# ClockV0_1.net
KiCad netlist of a schematic drawn in EAGLE
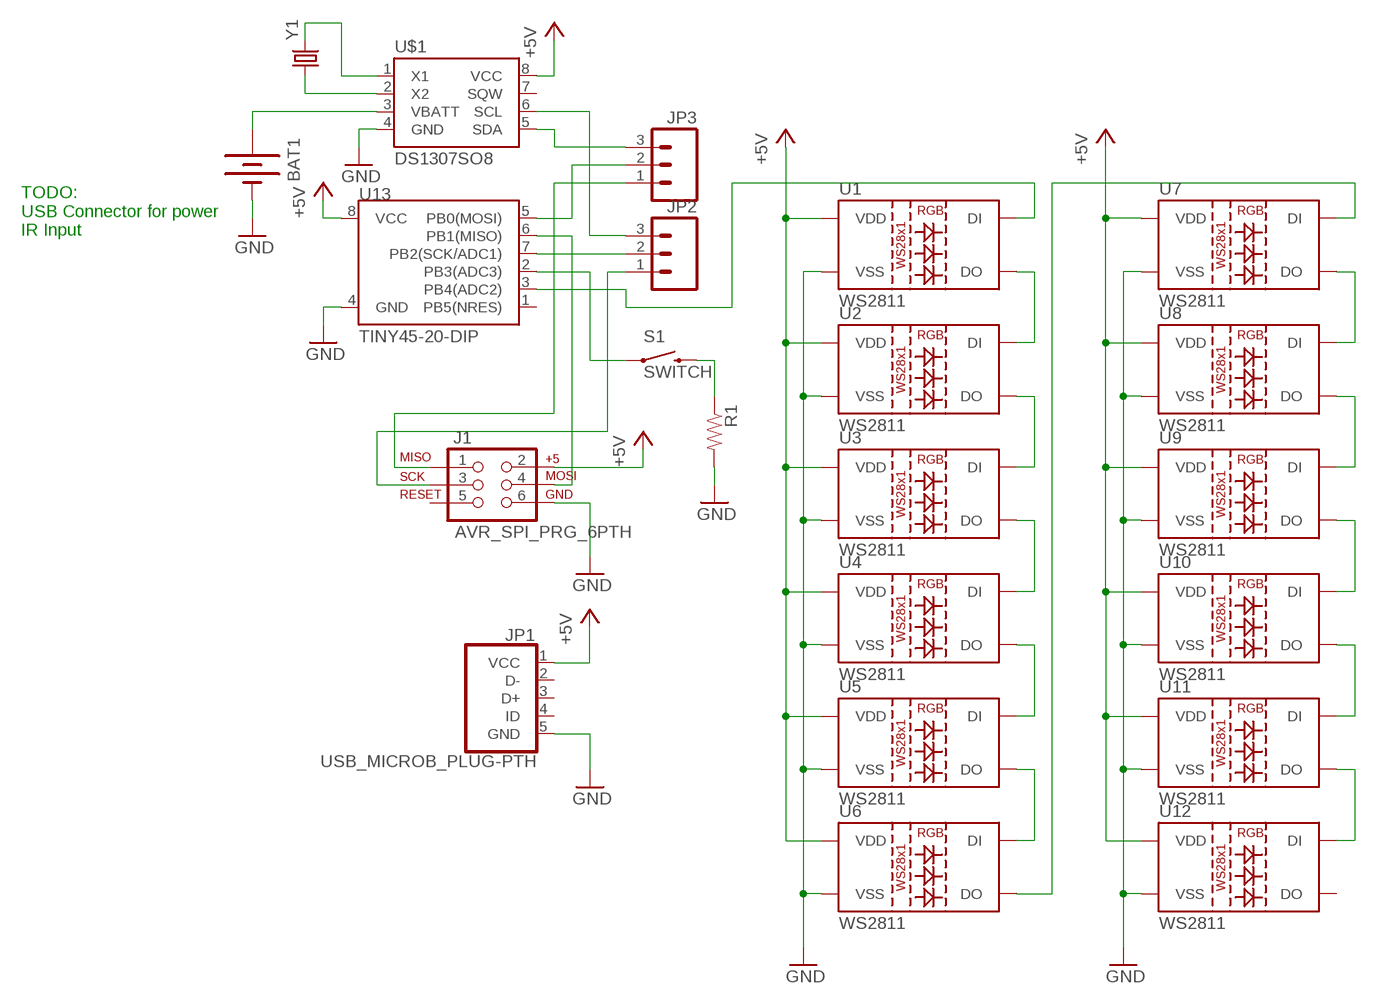
[diagram p0: schematic, sheet 1]

(export (version "E")
  (design (tool "Eeschema 10.0.6"))
  (components
    (comp (ref "BAT1")
      (value "BATTERY12PTH")
      (footprint "eagle-import:BATTCON_12MM_PTH")
      (libsource (lib "eagle-import") (part "BATTERY12PTH"))
    )
    (comp (ref "J1")
      (value "AVR_SPI_PRG_6PTH")
      (footprint "eagle-import:2X3")
      (libsource (lib "eagle-import") (part "AVR_SPI_PRG_6PTH"))
    )
    (comp (ref "JP1")
      (value "USB_MICROB_PLUG-PTH")
      (footprint "eagle-import:MICRO-B-RA-TH")
      (libsource (lib "eagle-import") (part "USB_MICROB_PLUG-PTH"))
    )
    (comp (ref "JP2")
      (value "M03PTH")
      (footprint "eagle-import:1X03")
      (libsource (lib "eagle-import") (part "M03PTH"))
    )
    (comp (ref "JP3")
      (value "M03PTH")
      (footprint "eagle-import:1X03")
      (libsource (lib "eagle-import") (part "M03PTH"))
    )
    (comp (ref "R1")
      (value "RESISTORPTH-1/2W")
      (footprint "eagle-import:AXIAL-0.5")
      (libsource (lib "eagle-import") (part "RESISTORPTH-1/2W"))
    )
    (comp (ref "S1")
      (value "SWITCH")
      (footprint "eagle-import:TACTILE-PTH")
      (libsource (lib "eagle-import") (part "SWITCH-MOMENTARY-2PTH"))
    )
    (comp (ref "U$1")
      (value "DS1307SO8")
      (footprint "eagle-import:SO08")
      (libsource (lib "eagle-import") (part "DS1307SO8"))
    )
    (comp (ref "U1")
      (value "WS2811")
      (footprint "eagle-import:LED-TRICOLOR-5050-IC")
      (libsource (lib "eagle-import") (part "LED-TRICOLOR-5050-ICWS2811"))
    )
    (comp (ref "U2")
      (value "WS2811")
      (footprint "eagle-import:LED-TRICOLOR-5050-IC")
      (libsource (lib "eagle-import") (part "LED-TRICOLOR-5050-ICWS2811"))
    )
    (comp (ref "U3")
      (value "WS2811")
      (footprint "eagle-import:LED-TRICOLOR-5050-IC")
      (libsource (lib "eagle-import") (part "LED-TRICOLOR-5050-ICWS2811"))
    )
    (comp (ref "U4")
      (value "WS2811")
      (footprint "eagle-import:LED-TRICOLOR-5050-IC")
      (libsource (lib "eagle-import") (part "LED-TRICOLOR-5050-ICWS2811"))
    )
    (comp (ref "U5")
      (value "WS2811")
      (footprint "eagle-import:LED-TRICOLOR-5050-IC")
      (libsource (lib "eagle-import") (part "LED-TRICOLOR-5050-ICWS2811"))
    )
    (comp (ref "U6")
      (value "WS2811")
      (footprint "eagle-import:LED-TRICOLOR-5050-IC")
      (libsource (lib "eagle-import") (part "LED-TRICOLOR-5050-ICWS2811"))
    )
    (comp (ref "U7")
      (value "WS2811")
      (footprint "eagle-import:LED-TRICOLOR-5050-IC")
      (libsource (lib "eagle-import") (part "LED-TRICOLOR-5050-ICWS2811"))
    )
    (comp (ref "U8")
      (value "WS2811")
      (footprint "eagle-import:LED-TRICOLOR-5050-IC")
      (libsource (lib "eagle-import") (part "LED-TRICOLOR-5050-ICWS2811"))
    )
    (comp (ref "U9")
      (value "WS2811")
      (footprint "eagle-import:LED-TRICOLOR-5050-IC")
      (libsource (lib "eagle-import") (part "LED-TRICOLOR-5050-ICWS2811"))
    )
    (comp (ref "U10")
      (value "WS2811")
      (footprint "eagle-import:LED-TRICOLOR-5050-IC")
      (libsource (lib "eagle-import") (part "LED-TRICOLOR-5050-ICWS2811"))
    )
    (comp (ref "U11")
      (value "WS2811")
      (footprint "eagle-import:LED-TRICOLOR-5050-IC")
      (libsource (lib "eagle-import") (part "LED-TRICOLOR-5050-ICWS2811"))
    )
    (comp (ref "U12")
      (value "WS2811")
      (footprint "eagle-import:LED-TRICOLOR-5050-IC")
      (libsource (lib "eagle-import") (part "LED-TRICOLOR-5050-ICWS2811"))
    )
    (comp (ref "U13")
      (value "TINY45-20-DIP")
      (footprint "eagle-import:DIP08")
      (libsource (lib "eagle-import") (part "ATTINY45TINY45-20-DIP"))
    )
    (comp (ref "Y1")
      (value "CRYSTAL32-SMD")
      (footprint "eagle-import:CRYSTAL-32KHZ-SMD")
      (libsource (lib "eagle-import") (part "CRYSTAL32-SMD"))
    )
  )
  (nets
    (net (code "1") (name "+5V") (class "Default")
      (node (ref "J1") (pin "2") (pinfunction "2_2") (pintype "passive"))
      (node (ref "JP1") (pin "1") (pinfunction "VCC_1") (pintype "bidirectional"))
      (node (ref "U$1") (pin "8") (pinfunction "VCC_8") (pintype "bidirectional"))
      (node (ref "U1") (pin "3") (pinfunction "VDD_3") (pintype "bidirectional"))
      (node (ref "U1") (pin "5") (pinfunction "VDD_5") (pintype "bidirectional"))
      (node (ref "U10") (pin "3") (pinfunction "VDD_3") (pintype "bidirectional"))
      (node (ref "U10") (pin "5") (pinfunction "VDD_5") (pintype "bidirectional"))
      (node (ref "U11") (pin "3") (pinfunction "VDD_3") (pintype "bidirectional"))
      (node (ref "U11") (pin "5") (pinfunction "VDD_5") (pintype "bidirectional"))
      (node (ref "U12") (pin "3") (pinfunction "VDD_3") (pintype "bidirectional"))
      (node (ref "U12") (pin "5") (pinfunction "VDD_5") (pintype "bidirectional"))
      (node (ref "U13") (pin "8") (pinfunction "VCC_8") (pintype "bidirectional"))
      (node (ref "U2") (pin "3") (pinfunction "VDD_3") (pintype "bidirectional"))
      (node (ref "U2") (pin "5") (pinfunction "VDD_5") (pintype "bidirectional"))
      (node (ref "U3") (pin "3") (pinfunction "VDD_3") (pintype "bidirectional"))
      (node (ref "U3") (pin "5") (pinfunction "VDD_5") (pintype "bidirectional"))
      (node (ref "U4") (pin "3") (pinfunction "VDD_3") (pintype "bidirectional"))
      (node (ref "U4") (pin "5") (pinfunction "VDD_5") (pintype "bidirectional"))
      (node (ref "U5") (pin "3") (pinfunction "VDD_3") (pintype "bidirectional"))
      (node (ref "U5") (pin "5") (pinfunction "VDD_5") (pintype "bidirectional"))
      (node (ref "U6") (pin "3") (pinfunction "VDD_3") (pintype "bidirectional"))
      (node (ref "U6") (pin "5") (pinfunction "VDD_5") (pintype "bidirectional"))
      (node (ref "U7") (pin "3") (pinfunction "VDD_3") (pintype "bidirectional"))
      (node (ref "U7") (pin "5") (pinfunction "VDD_5") (pintype "bidirectional"))
      (node (ref "U8") (pin "3") (pinfunction "VDD_3") (pintype "bidirectional"))
      (node (ref "U8") (pin "5") (pinfunction "VDD_5") (pintype "bidirectional"))
      (node (ref "U9") (pin "3") (pinfunction "VDD_3") (pintype "bidirectional"))
      (node (ref "U9") (pin "5") (pinfunction "VDD_5") (pintype "bidirectional"))
    )
    (net (code "2") (name "GND") (class "Default")
      (node (ref "BAT1") (pin "GND") (pinfunction "-_GND") (pintype "power_in"))
      (node (ref "J1") (pin "6") (pinfunction "6_6") (pintype "passive"))
      (node (ref "JP1") (pin "5") (pinfunction "GND_5") (pintype "bidirectional"))
      (node (ref "R1") (pin "P$2") (pinfunction "2_P$2") (pintype "passive"))
      (node (ref "U$1") (pin "4") (pinfunction "GND_4") (pintype "bidirectional"))
      (node (ref "U1") (pin "6") (pinfunction "VSS_6") (pintype "bidirectional"))
      (node (ref "U10") (pin "6") (pinfunction "VSS_6") (pintype "bidirectional"))
      (node (ref "U11") (pin "6") (pinfunction "VSS_6") (pintype "bidirectional"))
      (node (ref "U12") (pin "6") (pinfunction "VSS_6") (pintype "bidirectional"))
      (node (ref "U13") (pin "4") (pinfunction "GND_4") (pintype "bidirectional"))
      (node (ref "U2") (pin "6") (pinfunction "VSS_6") (pintype "bidirectional"))
      (node (ref "U3") (pin "6") (pinfunction "VSS_6") (pintype "bidirectional"))
      (node (ref "U4") (pin "6") (pinfunction "VSS_6") (pintype "bidirectional"))
      (node (ref "U5") (pin "6") (pinfunction "VSS_6") (pintype "bidirectional"))
      (node (ref "U6") (pin "6") (pinfunction "VSS_6") (pintype "bidirectional"))
      (node (ref "U7") (pin "6") (pinfunction "VSS_6") (pintype "bidirectional"))
      (node (ref "U8") (pin "6") (pinfunction "VSS_6") (pintype "bidirectional"))
      (node (ref "U9") (pin "6") (pinfunction "VSS_6") (pintype "bidirectional"))
    )
    (net (code "3") (name "Net-(BAT1-+)") (class "Default")
      (node (ref "BAT1") (pin "VCC@1") (pinfunction "+_VCC@1") (pintype "power_in"))
      (node (ref "U$1") (pin "3") (pinfunction "VBATT_3") (pintype "bidirectional"))
    )
    (net (code "4") (name "Net-(J1-Pad1)") (class "Default")
      (node (ref "J1") (pin "1") (pinfunction "1_1") (pintype "passive"))
      (node (ref "JP3") (pin "1") (pinfunction "1_1") (pintype "passive"))
    )
    (net (code "5") (name "Net-(J1-Pad3)") (class "Default")
      (node (ref "J1") (pin "3") (pinfunction "3_3") (pintype "passive"))
      (node (ref "JP2") (pin "1") (pinfunction "1_1") (pintype "passive"))
    )
    (net (code "6") (name "Net-(R1-1)") (class "Default")
      (node (ref "R1") (pin "P$1") (pinfunction "1_P$1") (pintype "passive"))
      (node (ref "S1") (pin "3") (pinfunction "2_3") (pintype "passive"))
    )
    (net (code "7") (name "Net-(U$1-SCL)") (class "Default")
      (node (ref "JP2") (pin "3") (pinfunction "3_3") (pintype "passive"))
      (node (ref "U$1") (pin "6") (pinfunction "SCL_6") (pintype "bidirectional"))
    )
    (net (code "8") (name "Net-(U$1-SDA)") (class "Default")
      (node (ref "JP3") (pin "3") (pinfunction "3_3") (pintype "passive"))
      (node (ref "U$1") (pin "5") (pinfunction "SDA_5") (pintype "bidirectional"))
    )
    (net (code "9") (name "Net-(U$1-X1)") (class "Default")
      (node (ref "U$1") (pin "1") (pinfunction "X1_1") (pintype "bidirectional"))
      (node (ref "Y1") (pin "X2") (pinfunction "2_X2") (pintype "passive"))
    )
    (net (code "10") (name "Net-(U$1-X2)") (class "Default")
      (node (ref "U$1") (pin "2") (pinfunction "X2_2") (pintype "bidirectional"))
      (node (ref "Y1") (pin "X1") (pinfunction "1_X1") (pintype "passive"))
    )
    (net (code "11") (name "Net-(U1-DI)") (class "Default")
      (node (ref "U1") (pin "2") (pinfunction "DI_2") (pintype "bidirectional"))
      (node (ref "U13") (pin "3") (pinfunction "PB4(ADC2)_3") (pintype "bidirectional"))
    )
    (net (code "12") (name "Net-(U1-DO)") (class "Default")
      (node (ref "U1") (pin "1") (pinfunction "DO_1") (pintype "bidirectional"))
      (node (ref "U2") (pin "2") (pinfunction "DI_2") (pintype "bidirectional"))
    )
    (net (code "13") (name "Net-(U2-DO)") (class "Default")
      (node (ref "U2") (pin "1") (pinfunction "DO_1") (pintype "bidirectional"))
      (node (ref "U3") (pin "2") (pinfunction "DI_2") (pintype "bidirectional"))
    )
    (net (code "14") (name "Net-(U3-DO)") (class "Default")
      (node (ref "U3") (pin "1") (pinfunction "DO_1") (pintype "bidirectional"))
      (node (ref "U4") (pin "2") (pinfunction "DI_2") (pintype "bidirectional"))
    )
    (net (code "15") (name "Net-(U4-DO)") (class "Default")
      (node (ref "U4") (pin "1") (pinfunction "DO_1") (pintype "bidirectional"))
      (node (ref "U5") (pin "2") (pinfunction "DI_2") (pintype "bidirectional"))
    )
    (net (code "16") (name "Net-(U5-DO)") (class "Default")
      (node (ref "U5") (pin "1") (pinfunction "DO_1") (pintype "bidirectional"))
      (node (ref "U6") (pin "2") (pinfunction "DI_2") (pintype "bidirectional"))
    )
    (net (code "17") (name "Net-(U6-DO)") (class "Default")
      (node (ref "U6") (pin "1") (pinfunction "DO_1") (pintype "bidirectional"))
      (node (ref "U7") (pin "2") (pinfunction "DI_2") (pintype "bidirectional"))
    )
    (net (code "18") (name "Net-(U7-DO)") (class "Default")
      (node (ref "U7") (pin "1") (pinfunction "DO_1") (pintype "bidirectional"))
      (node (ref "U8") (pin "2") (pinfunction "DI_2") (pintype "bidirectional"))
    )
    (net (code "19") (name "Net-(U8-DO)") (class "Default")
      (node (ref "U8") (pin "1") (pinfunction "DO_1") (pintype "bidirectional"))
      (node (ref "U9") (pin "2") (pinfunction "DI_2") (pintype "bidirectional"))
    )
    (net (code "20") (name "Net-(U10-DI)") (class "Default")
      (node (ref "U10") (pin "2") (pinfunction "DI_2") (pintype "bidirectional"))
      (node (ref "U9") (pin "1") (pinfunction "DO_1") (pintype "bidirectional"))
    )
    (net (code "21") (name "Net-(U10-DO)") (class "Default")
      (node (ref "U10") (pin "1") (pinfunction "DO_1") (pintype "bidirectional"))
      (node (ref "U11") (pin "2") (pinfunction "DI_2") (pintype "bidirectional"))
    )
    (net (code "22") (name "Net-(U11-DO)") (class "Default")
      (node (ref "U11") (pin "1") (pinfunction "DO_1") (pintype "bidirectional"))
      (node (ref "U12") (pin "2") (pinfunction "DI_2") (pintype "bidirectional"))
    )
    (net (code "23") (name "Net-(U13-PB0(MOSI))") (class "Default")
      (node (ref "JP3") (pin "2") (pinfunction "2_2") (pintype "passive"))
      (node (ref "U13") (pin "5") (pinfunction "PB0(MOSI)_5") (pintype "bidirectional"))
    )
    (net (code "24") (name "Net-(U13-PB1(MISO))") (class "Default")
      (node (ref "J1") (pin "4") (pinfunction "4_4") (pintype "passive"))
      (node (ref "U13") (pin "6") (pinfunction "PB1(MISO)_6") (pintype "bidirectional"))
    )
    (net (code "25") (name "Net-(U13-PB2(SCK{slash}ADC1))") (class "Default")
      (node (ref "JP2") (pin "2") (pinfunction "2_2") (pintype "passive"))
      (node (ref "U13") (pin "7") (pinfunction "PB2(SCK/ADC1)_7") (pintype "bidirectional"))
    )
    (net (code "26") (name "Net-(U13-PB3(ADC3))") (class "Default")
      (node (ref "S1") (pin "1") (pinfunction "1_1") (pintype "passive"))
      (node (ref "U13") (pin "2") (pinfunction "PB3(ADC3)_2") (pintype "bidirectional"))
    )
    (net (code "27") (name "unconnected-(J1-Pad5)") (class "Default")
      (node (ref "J1") (pin "5") (pinfunction "5_5") (pintype "passive"))
    )
    (net (code "28") (name "unconnected-(JP1-D+-Pad3)") (class "Default")
      (node (ref "JP1") (pin "3") (pinfunction "D+_3") (pintype "bidirectional"))
    )
    (net (code "29") (name "unconnected-(JP1-D--Pad2)") (class "Default")
      (node (ref "JP1") (pin "2") (pinfunction "D-_2") (pintype "bidirectional"))
    )
    (net (code "30") (name "unconnected-(JP1-ID-Pad4)") (class "Default")
      (node (ref "JP1") (pin "4") (pinfunction "ID_4") (pintype "bidirectional"))
    )
    (net (code "31") (name "unconnected-(U$1-SQW-Pad7)") (class "Default")
      (node (ref "U$1") (pin "7") (pinfunction "SQW_7") (pintype "bidirectional"))
    )
    (net (code "32") (name "unconnected-(U12-DO-Pad1)") (class "Default")
      (node (ref "U12") (pin "1") (pinfunction "DO_1") (pintype "bidirectional"))
    )
    (net (code "33") (name "unconnected-(U13-PB5(NRES)-Pad1)") (class "Default")
      (node (ref "U13") (pin "1") (pinfunction "PB5(NRES)_1") (pintype "bidirectional"))
    )
  )
)
